# SCH_leanRA_2024-04-03.net
KiCad netlist of a schematic drawn in EasyEDA
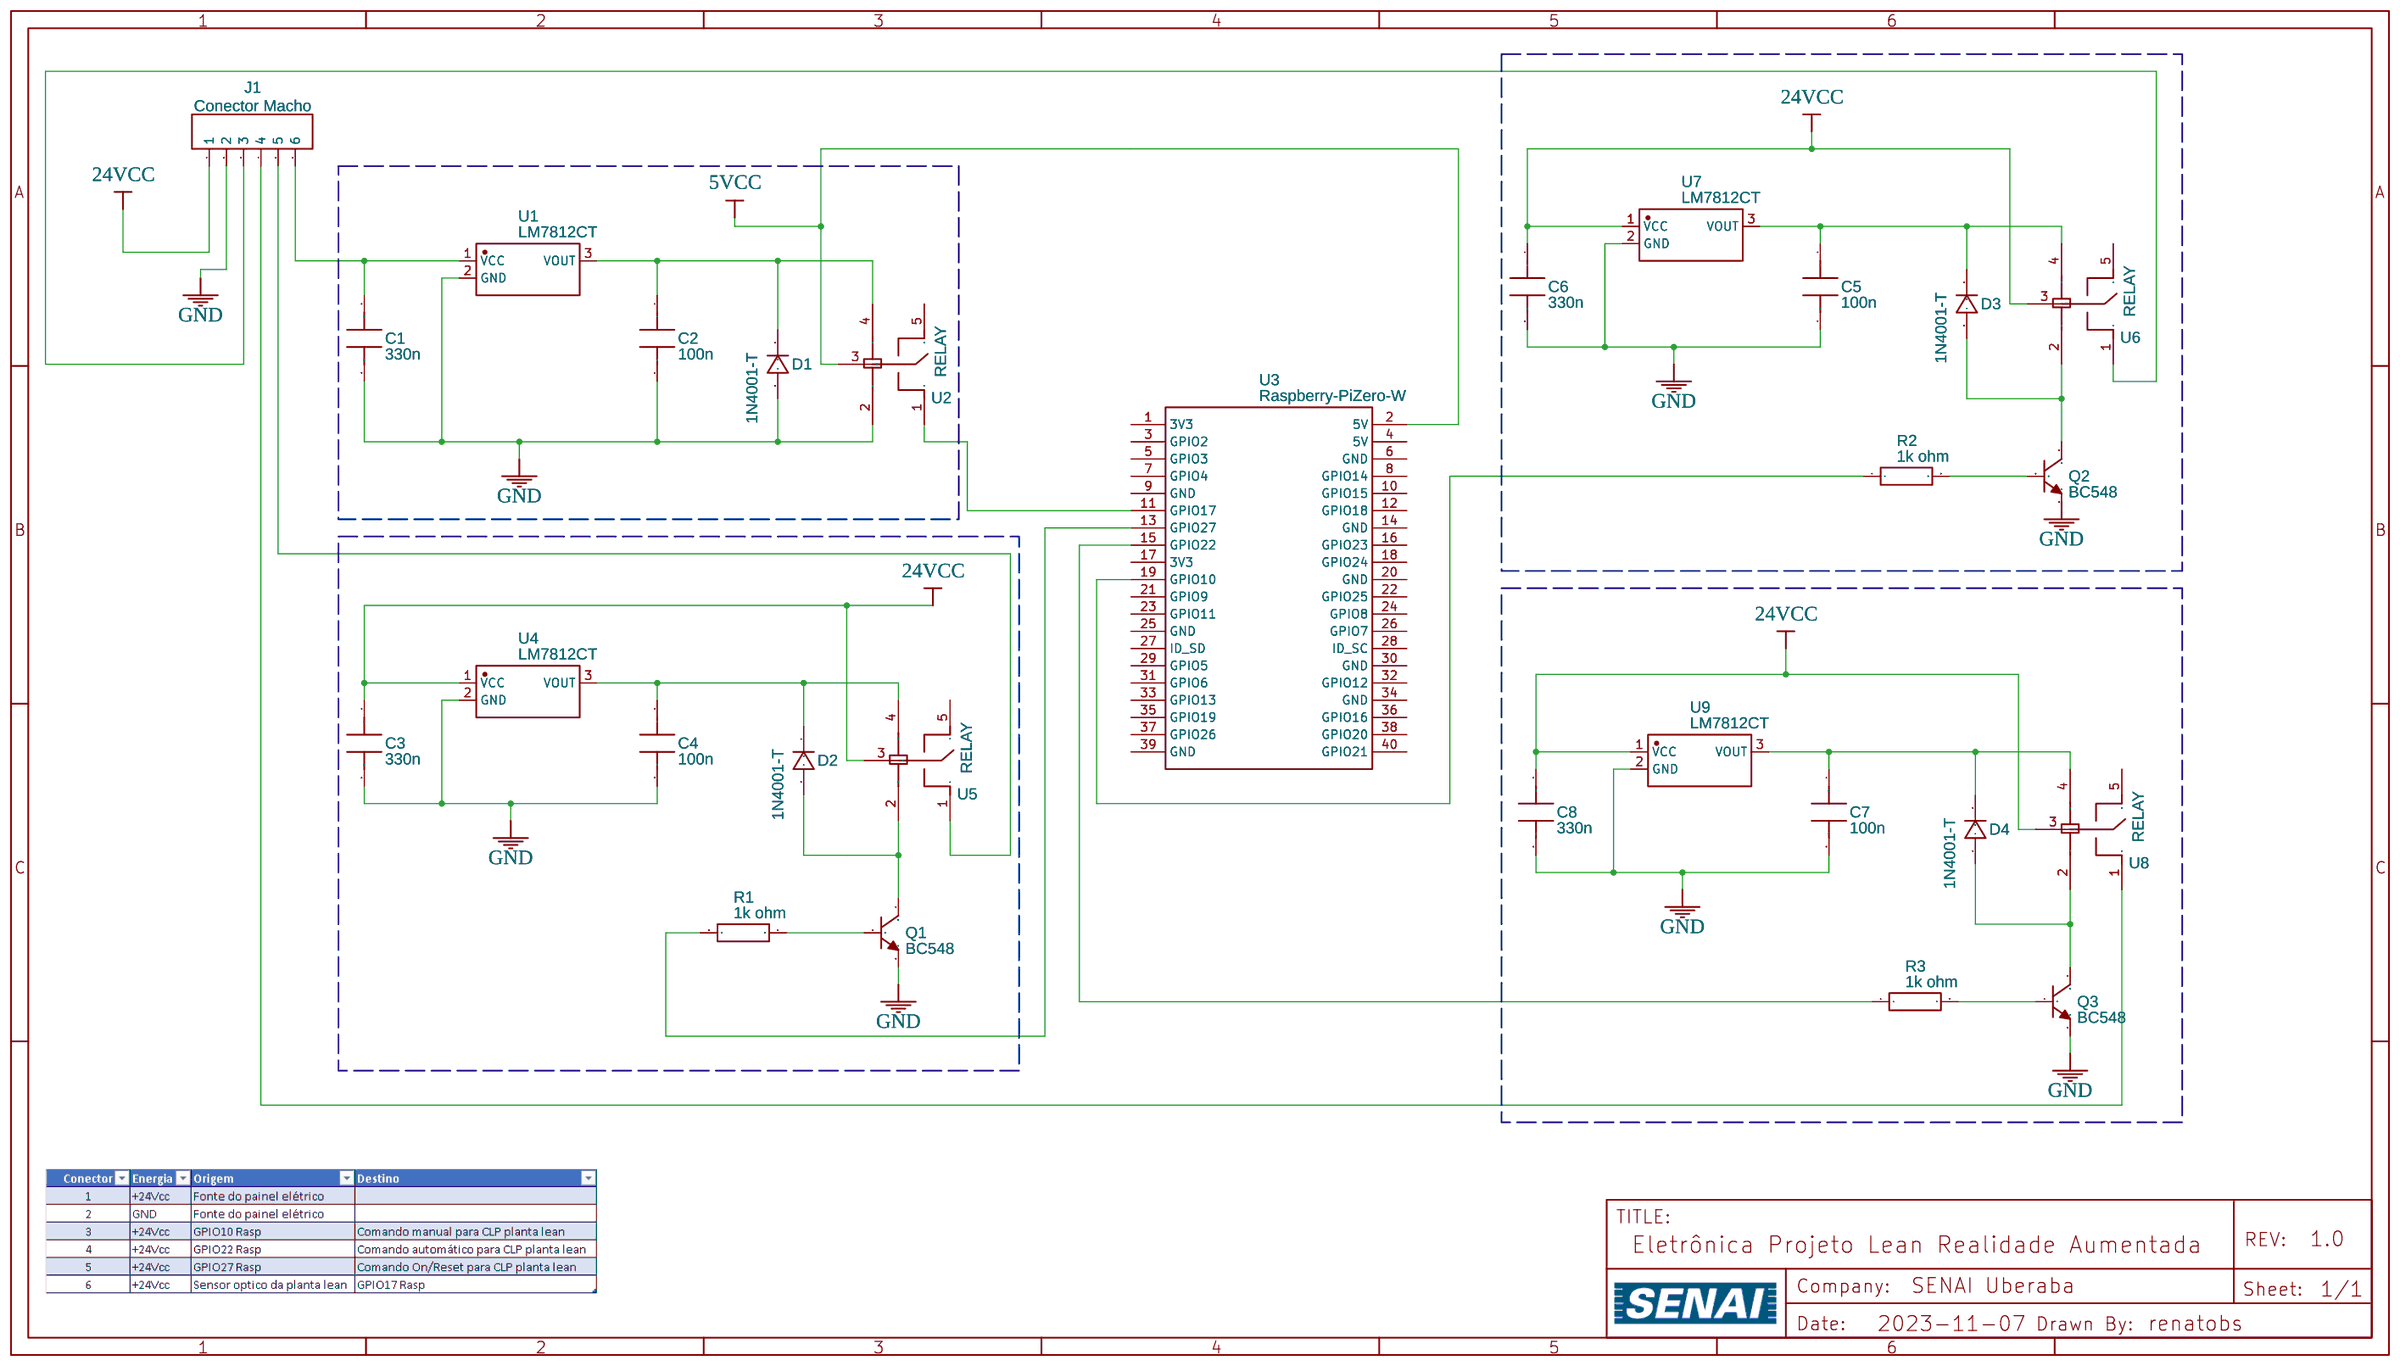
[diagram p0: schematic sheet]

(export (version "E")
  (design (tool "Eeschema 10.0.6"))
  (components
    (comp (ref "C1") (value "330n") (libsource (lib "") (part "DISC CAPACITOR COPY")))
    (comp (ref "C2") (value "100n") (libsource (lib "") (part "DISC CAPACITOR COPY")))
    (comp (ref "C3") (value "330n") (libsource (lib "") (part "DISC CAPACITOR COPY")))
    (comp (ref "C4") (value "100n") (libsource (lib "") (part "DISC CAPACITOR COPY")))
    (comp (ref "C5") (value "100n") (libsource (lib "") (part "DISC CAPACITOR COPY")))
    (comp (ref "C6") (value "330n") (libsource (lib "") (part "DISC CAPACITOR COPY")))
    (comp (ref "C7") (value "100n") (libsource (lib "") (part "DISC CAPACITOR COPY")))
    (comp (ref "C8") (value "330n") (libsource (lib "") (part "DISC CAPACITOR COPY")))
    (comp (ref "D1")
      (value "1N4001-T")
      (fields (field (name "Manufacturer") "DIODES(美台)"))
      (libsource (lib "") (part "1N4001-T"))
    )
    (comp (ref "D2")
      (value "1N4001-T")
      (fields (field (name "Manufacturer") "DIODES(美台)"))
      (libsource (lib "") (part "1N4001-T"))
    )
    (comp (ref "D3")
      (value "1N4001-T")
      (fields (field (name "Manufacturer") "DIODES(美台)"))
      (libsource (lib "") (part "1N4001-T"))
    )
    (comp (ref "D4")
      (value "1N4001-T")
      (fields (field (name "Manufacturer") "DIODES(美台)"))
      (libsource (lib "") (part "1N4001-T"))
    )
    (comp (ref "J1") (value "Conector Macho") (libsource (lib "") (part "HDR-M-2.54_1x6")))
    (comp (ref "Q1")
      (value "BC548")
      (fields (field (name "Manufacturer Part") "BC.548") (field (name "Manufacturer") "Officine PADANE"))
      (libsource (lib "") (part "BC548"))
    )
    (comp (ref "Q2")
      (value "BC548")
      (fields (field (name "Manufacturer Part") "BC.548") (field (name "Manufacturer") "Officine PADANE"))
      (libsource (lib "") (part "BC548"))
    )
    (comp (ref "Q3")
      (value "BC548")
      (fields (field (name "Manufacturer Part") "BC.548") (field (name "Manufacturer") "Officine PADANE"))
      (libsource (lib "") (part "BC548"))
    )
    (comp (ref "R1") (value "1k ohm") (libsource (lib "") (part "RESISTOR 1/4")))
    (comp (ref "R2") (value "1k ohm") (libsource (lib "") (part "RESISTOR 1/4")))
    (comp (ref "R3") (value "1k ohm") (libsource (lib "") (part "RESISTOR 1/4")))
    (comp (ref "U1")
      (value "LM7812CT")
      (fields (field (name "Manufacturer") "HGSEMI(华冠)"))
      (libsource (lib "") (part "LM7812CT"))
    )
    (comp (ref "U2")
      (value "RELAY")
      (fields (field (name "Manufacturer Part") "Relay-SPST"))
      (libsource (lib "") (part "RELAY-SPST"))
    )
    (comp (ref "U3") (value "Raspberry-PiZero-W") (libsource (lib "") (part "Raspberry-PiZero-W")))
    (comp (ref "U4")
      (value "LM7812CT")
      (fields (field (name "Manufacturer") "HGSEMI(华冠)"))
      (libsource (lib "") (part "LM7812CT"))
    )
    (comp (ref "U5")
      (value "RELAY")
      (fields (field (name "Manufacturer Part") "Relay-SPST"))
      (libsource (lib "") (part "RELAY-SPST"))
    )
    (comp (ref "U6")
      (value "RELAY")
      (fields (field (name "Manufacturer Part") "Relay-SPST"))
      (libsource (lib "") (part "RELAY-SPST"))
    )
    (comp (ref "U7")
      (value "LM7812CT")
      (fields (field (name "Manufacturer") "HGSEMI(华冠)"))
      (libsource (lib "") (part "LM7812CT"))
    )
    (comp (ref "U8")
      (value "RELAY")
      (fields (field (name "Manufacturer Part") "Relay-SPST"))
      (libsource (lib "") (part "RELAY-SPST"))
    )
    (comp (ref "U9")
      (value "LM7812CT")
      (fields (field (name "Manufacturer") "HGSEMI(华冠)"))
      (libsource (lib "") (part "LM7812CT"))
    )
  )
  (nets
    (net (code "1") (name "5VCC") (class "Default")
      (node (ref "U2") (pin "3") (pinfunction "3_3") (pintype "unspecified"))
      (node (ref "U3") (pin "2") (pinfunction "5V_2") (pintype "unspecified"))
    )
    (net (code "2") (name "24VCC") (class "Default")
      (node (ref "C3") (pin "1") (pinfunction "1_1") (pintype "unspecified"))
      (node (ref "C6") (pin "1") (pinfunction "1_1") (pintype "unspecified"))
      (node (ref "C8") (pin "1") (pinfunction "1_1") (pintype "unspecified"))
      (node (ref "J1") (pin "1") (pinfunction "1_1") (pintype "input"))
      (node (ref "U4") (pin "1") (pinfunction "VCC_1") (pintype "unspecified"))
      (node (ref "U5") (pin "3") (pinfunction "3_3") (pintype "unspecified"))
      (node (ref "U6") (pin "3") (pinfunction "3_3") (pintype "unspecified"))
      (node (ref "U7") (pin "1") (pinfunction "VCC_1") (pintype "unspecified"))
      (node (ref "U8") (pin "3") (pinfunction "3_3") (pintype "unspecified"))
      (node (ref "U9") (pin "1") (pinfunction "VCC_1") (pintype "unspecified"))
    )
    (net (code "3") (name "GND") (class "Default")
      (node (ref "C1") (pin "2") (pinfunction "2_2") (pintype "unspecified"))
      (node (ref "C2") (pin "2") (pinfunction "2_2") (pintype "unspecified"))
      (node (ref "C3") (pin "2") (pinfunction "2_2") (pintype "unspecified"))
      (node (ref "C4") (pin "2") (pinfunction "2_2") (pintype "unspecified"))
      (node (ref "C5") (pin "2") (pinfunction "2_2") (pintype "unspecified"))
      (node (ref "C6") (pin "2") (pinfunction "2_2") (pintype "unspecified"))
      (node (ref "C7") (pin "2") (pinfunction "2_2") (pintype "unspecified"))
      (node (ref "C8") (pin "2") (pinfunction "2_2") (pintype "unspecified"))
      (node (ref "D1") (pin "2") (pinfunction "A_2") (pintype "unspecified"))
      (node (ref "J1") (pin "2") (pinfunction "2_2") (pintype "input"))
      (node (ref "Q1") (pin "3") (pinfunction "E_3") (pintype "unspecified"))
      (node (ref "Q2") (pin "3") (pinfunction "E_3") (pintype "unspecified"))
      (node (ref "Q3") (pin "3") (pinfunction "E_3") (pintype "unspecified"))
      (node (ref "U1") (pin "2") (pinfunction "GND_2") (pintype "unspecified"))
      (node (ref "U2") (pin "2") (pinfunction "2_2") (pintype "unspecified"))
      (node (ref "U4") (pin "2") (pinfunction "GND_2") (pintype "unspecified"))
      (node (ref "U7") (pin "2") (pinfunction "GND_2") (pintype "unspecified"))
      (node (ref "U9") (pin "2") (pinfunction "GND_2") (pintype "unspecified"))
    )
    (net (code "4") (name "Net-(D1-C)") (class "Default")
      (node (ref "C2") (pin "1") (pinfunction "1_1") (pintype "unspecified"))
      (node (ref "D1") (pin "1") (pinfunction "C_1") (pintype "unspecified"))
      (node (ref "U1") (pin "3") (pinfunction "VOUT_3") (pintype "unspecified"))
      (node (ref "U2") (pin "4") (pinfunction "4_4") (pintype "unspecified"))
    )
    (net (code "5") (name "Net-(D2-A)") (class "Default")
      (node (ref "D2") (pin "2") (pinfunction "A_2") (pintype "unspecified"))
      (node (ref "Q1") (pin "1") (pinfunction "C_1") (pintype "unspecified"))
      (node (ref "U5") (pin "2") (pinfunction "2_2") (pintype "unspecified"))
    )
    (net (code "6") (name "Net-(D2-C)") (class "Default")
      (node (ref "C4") (pin "1") (pinfunction "1_1") (pintype "unspecified"))
      (node (ref "D2") (pin "1") (pinfunction "C_1") (pintype "unspecified"))
      (node (ref "U4") (pin "3") (pinfunction "VOUT_3") (pintype "unspecified"))
      (node (ref "U5") (pin "4") (pinfunction "4_4") (pintype "unspecified"))
    )
    (net (code "7") (name "Net-(D3-A)") (class "Default")
      (node (ref "D3") (pin "2") (pinfunction "A_2") (pintype "unspecified"))
      (node (ref "Q2") (pin "1") (pinfunction "C_1") (pintype "unspecified"))
      (node (ref "U6") (pin "2") (pinfunction "2_2") (pintype "unspecified"))
    )
    (net (code "8") (name "Net-(D3-C)") (class "Default")
      (node (ref "C5") (pin "1") (pinfunction "1_1") (pintype "unspecified"))
      (node (ref "D3") (pin "1") (pinfunction "C_1") (pintype "unspecified"))
      (node (ref "U6") (pin "4") (pinfunction "4_4") (pintype "unspecified"))
      (node (ref "U7") (pin "3") (pinfunction "VOUT_3") (pintype "unspecified"))
    )
    (net (code "9") (name "Net-(D4-A)") (class "Default")
      (node (ref "D4") (pin "2") (pinfunction "A_2") (pintype "unspecified"))
      (node (ref "Q3") (pin "1") (pinfunction "C_1") (pintype "unspecified"))
      (node (ref "U8") (pin "2") (pinfunction "2_2") (pintype "unspecified"))
    )
    (net (code "10") (name "Net-(D4-C)") (class "Default")
      (node (ref "C7") (pin "1") (pinfunction "1_1") (pintype "unspecified"))
      (node (ref "D4") (pin "1") (pinfunction "C_1") (pintype "unspecified"))
      (node (ref "U8") (pin "4") (pinfunction "4_4") (pintype "unspecified"))
      (node (ref "U9") (pin "3") (pinfunction "VOUT_3") (pintype "unspecified"))
    )
    (net (code "11") (name "Net-(J1-Pad3)") (class "Default")
      (node (ref "J1") (pin "3") (pinfunction "3_3") (pintype "input"))
      (node (ref "U6") (pin "1") (pinfunction "1_1") (pintype "unspecified"))
    )
    (net (code "12") (name "Net-(J1-Pad4)") (class "Default")
      (node (ref "J1") (pin "4") (pinfunction "4_4") (pintype "input"))
      (node (ref "U8") (pin "1") (pinfunction "1_1") (pintype "unspecified"))
    )
    (net (code "13") (name "Net-(J1-Pad5)") (class "Default")
      (node (ref "J1") (pin "5") (pinfunction "5_5") (pintype "input"))
      (node (ref "U5") (pin "1") (pinfunction "1_1") (pintype "unspecified"))
    )
    (net (code "14") (name "Net-(Q1-B)") (class "Default")
      (node (ref "Q1") (pin "2") (pinfunction "B_2") (pintype "unspecified"))
      (node (ref "R1") (pin "2") (pinfunction "2_2") (pintype "unspecified"))
    )
    (net (code "15") (name "Net-(Q2-B)") (class "Default")
      (node (ref "Q2") (pin "2") (pinfunction "B_2") (pintype "unspecified"))
      (node (ref "R2") (pin "2") (pinfunction "2_2") (pintype "unspecified"))
    )
    (net (code "16") (name "Net-(Q3-B)") (class "Default")
      (node (ref "Q3") (pin "2") (pinfunction "B_2") (pintype "unspecified"))
      (node (ref "R3") (pin "2") (pinfunction "2_2") (pintype "unspecified"))
    )
    (net (code "17") (name "Net-(U1-VCC)") (class "Default")
      (node (ref "C1") (pin "1") (pinfunction "1_1") (pintype "unspecified"))
      (node (ref "J1") (pin "6") (pinfunction "6_6") (pintype "input"))
      (node (ref "U1") (pin "1") (pinfunction "VCC_1") (pintype "unspecified"))
    )
    (net (code "18") (name "Net-(U3-GPIO10)") (class "Default")
      (node (ref "R2") (pin "1") (pinfunction "1_1") (pintype "unspecified"))
      (node (ref "U3") (pin "19") (pinfunction "GPIO10_19") (pintype "unspecified"))
    )
    (net (code "19") (name "Net-(U3-GPIO17)") (class "Default")
      (node (ref "U2") (pin "1") (pinfunction "1_1") (pintype "unspecified"))
      (node (ref "U3") (pin "11") (pinfunction "GPIO17_11") (pintype "unspecified"))
    )
    (net (code "20") (name "Net-(U3-GPIO22)") (class "Default")
      (node (ref "R3") (pin "1") (pinfunction "1_1") (pintype "unspecified"))
      (node (ref "U3") (pin "15") (pinfunction "GPIO22_15") (pintype "unspecified"))
    )
    (net (code "21") (name "Net-(U3-GPIO27)") (class "Default")
      (node (ref "R1") (pin "1") (pinfunction "1_1") (pintype "unspecified"))
      (node (ref "U3") (pin "13") (pinfunction "GPIO27_13") (pintype "unspecified"))
    )
    (net (code "22") (name "unconnected-(U2-Pad5)") (class "Default")
      (node (ref "U2") (pin "5") (pinfunction "5_5") (pintype "unspecified"))
    )
    (net (code "23") (name "unconnected-(U3-3V3-Pad1)") (class "Default")
      (node (ref "U3") (pin "1") (pinfunction "3V3_1") (pintype "unspecified"))
    )
    (net (code "24") (name "unconnected-(U3-3V3-Pad17)") (class "Default")
      (node (ref "U3") (pin "17") (pinfunction "3V3_17") (pintype "unspecified"))
    )
    (net (code "25") (name "unconnected-(U3-5V-Pad4)") (class "Default")
      (node (ref "U3") (pin "4") (pinfunction "5V_4") (pintype "unspecified"))
    )
    (net (code "26") (name "unconnected-(U3-GND-Pad6)") (class "Default")
      (node (ref "U3") (pin "6") (pinfunction "GND_6") (pintype "unspecified"))
    )
    (net (code "27") (name "unconnected-(U3-GND-Pad9)") (class "Default")
      (node (ref "U3") (pin "9") (pinfunction "GND_9") (pintype "unspecified"))
    )
    (net (code "28") (name "unconnected-(U3-GND-Pad14)") (class "Default")
      (node (ref "U3") (pin "14") (pinfunction "GND_14") (pintype "unspecified"))
    )
    (net (code "29") (name "unconnected-(U3-GND-Pad20)") (class "Default")
      (node (ref "U3") (pin "20") (pinfunction "GND_20") (pintype "unspecified"))
    )
    (net (code "30") (name "unconnected-(U3-GND-Pad25)") (class "Default")
      (node (ref "U3") (pin "25") (pinfunction "GND_25") (pintype "unspecified"))
    )
    (net (code "31") (name "unconnected-(U3-GND-Pad30)") (class "Default")
      (node (ref "U3") (pin "30") (pinfunction "GND_30") (pintype "unspecified"))
    )
    (net (code "32") (name "unconnected-(U3-GND-Pad34)") (class "Default")
      (node (ref "U3") (pin "34") (pinfunction "GND_34") (pintype "unspecified"))
    )
    (net (code "33") (name "unconnected-(U3-GND-Pad39)") (class "Default")
      (node (ref "U3") (pin "39") (pinfunction "GND_39") (pintype "unspecified"))
    )
    (net (code "34") (name "unconnected-(U3-GPIO2-Pad3)") (class "Default")
      (node (ref "U3") (pin "3") (pinfunction "GPIO2_3") (pintype "unspecified"))
    )
    (net (code "35") (name "unconnected-(U3-GPIO3-Pad5)") (class "Default")
      (node (ref "U3") (pin "5") (pinfunction "GPIO3_5") (pintype "unspecified"))
    )
    (net (code "36") (name "unconnected-(U3-GPIO4-Pad7)") (class "Default")
      (node (ref "U3") (pin "7") (pinfunction "GPIO4_7") (pintype "unspecified"))
    )
    (net (code "37") (name "unconnected-(U3-GPIO5-Pad29)") (class "Default")
      (node (ref "U3") (pin "29") (pinfunction "GPIO5_29") (pintype "unspecified"))
    )
    (net (code "38") (name "unconnected-(U3-GPIO6-Pad31)") (class "Default")
      (node (ref "U3") (pin "31") (pinfunction "GPIO6_31") (pintype "unspecified"))
    )
    (net (code "39") (name "unconnected-(U3-GPIO7-Pad26)") (class "Default")
      (node (ref "U3") (pin "26") (pinfunction "GPIO7_26") (pintype "unspecified"))
    )
    (net (code "40") (name "unconnected-(U3-GPIO8-Pad24)") (class "Default")
      (node (ref "U3") (pin "24") (pinfunction "GPIO8_24") (pintype "unspecified"))
    )
    (net (code "41") (name "unconnected-(U3-GPIO9-Pad21)") (class "Default")
      (node (ref "U3") (pin "21") (pinfunction "GPIO9_21") (pintype "unspecified"))
    )
    (net (code "42") (name "unconnected-(U3-GPIO11-Pad23)") (class "Default")
      (node (ref "U3") (pin "23") (pinfunction "GPIO11_23") (pintype "unspecified"))
    )
    (net (code "43") (name "unconnected-(U3-GPIO12-Pad32)") (class "Default")
      (node (ref "U3") (pin "32") (pinfunction "GPIO12_32") (pintype "unspecified"))
    )
    (net (code "44") (name "unconnected-(U3-GPIO13-Pad33)") (class "Default")
      (node (ref "U3") (pin "33") (pinfunction "GPIO13_33") (pintype "unspecified"))
    )
    (net (code "45") (name "unconnected-(U3-GPIO14-Pad8)") (class "Default")
      (node (ref "U3") (pin "8") (pinfunction "GPIO14_8") (pintype "unspecified"))
    )
    (net (code "46") (name "unconnected-(U3-GPIO15-Pad10)") (class "Default")
      (node (ref "U3") (pin "10") (pinfunction "GPIO15_10") (pintype "unspecified"))
    )
    (net (code "47") (name "unconnected-(U3-GPIO16-Pad36)") (class "Default")
      (node (ref "U3") (pin "36") (pinfunction "GPIO16_36") (pintype "unspecified"))
    )
    (net (code "48") (name "unconnected-(U3-GPIO18-Pad12)") (class "Default")
      (node (ref "U3") (pin "12") (pinfunction "GPIO18_12") (pintype "unspecified"))
    )
    (net (code "49") (name "unconnected-(U3-GPIO19-Pad35)") (class "Default")
      (node (ref "U3") (pin "35") (pinfunction "GPIO19_35") (pintype "unspecified"))
    )
    (net (code "50") (name "unconnected-(U3-GPIO20-Pad38)") (class "Default")
      (node (ref "U3") (pin "38") (pinfunction "GPIO20_38") (pintype "unspecified"))
    )
    (net (code "51") (name "unconnected-(U3-GPIO21-Pad40)") (class "Default")
      (node (ref "U3") (pin "40") (pinfunction "GPIO21_40") (pintype "unspecified"))
    )
    (net (code "52") (name "unconnected-(U3-GPIO23-Pad16)") (class "Default")
      (node (ref "U3") (pin "16") (pinfunction "GPIO23_16") (pintype "unspecified"))
    )
    (net (code "53") (name "unconnected-(U3-GPIO24-Pad18)") (class "Default")
      (node (ref "U3") (pin "18") (pinfunction "GPIO24_18") (pintype "unspecified"))
    )
    (net (code "54") (name "unconnected-(U3-GPIO25-Pad22)") (class "Default")
      (node (ref "U3") (pin "22") (pinfunction "GPIO25_22") (pintype "unspecified"))
    )
    (net (code "55") (name "unconnected-(U3-GPIO26-Pad37)") (class "Default")
      (node (ref "U3") (pin "37") (pinfunction "GPIO26_37") (pintype "unspecified"))
    )
    (net (code "56") (name "unconnected-(U3-ID_SC-Pad28)") (class "Default")
      (node (ref "U3") (pin "28") (pinfunction "ID_SC_28") (pintype "unspecified"))
    )
    (net (code "57") (name "unconnected-(U3-ID_SD-Pad27)") (class "Default")
      (node (ref "U3") (pin "27") (pinfunction "ID_SD_27") (pintype "unspecified"))
    )
    (net (code "58") (name "unconnected-(U5-Pad5)") (class "Default")
      (node (ref "U5") (pin "5") (pinfunction "5_5") (pintype "unspecified"))
    )
    (net (code "59") (name "unconnected-(U6-Pad5)") (class "Default")
      (node (ref "U6") (pin "5") (pinfunction "5_5") (pintype "unspecified"))
    )
    (net (code "60") (name "unconnected-(U8-Pad5)") (class "Default")
      (node (ref "U8") (pin "5") (pinfunction "5_5") (pintype "unspecified"))
    )
  )
)
